# moire_v1_2_rt.net
KiCad netlist of a schematic drawn in EAGLE
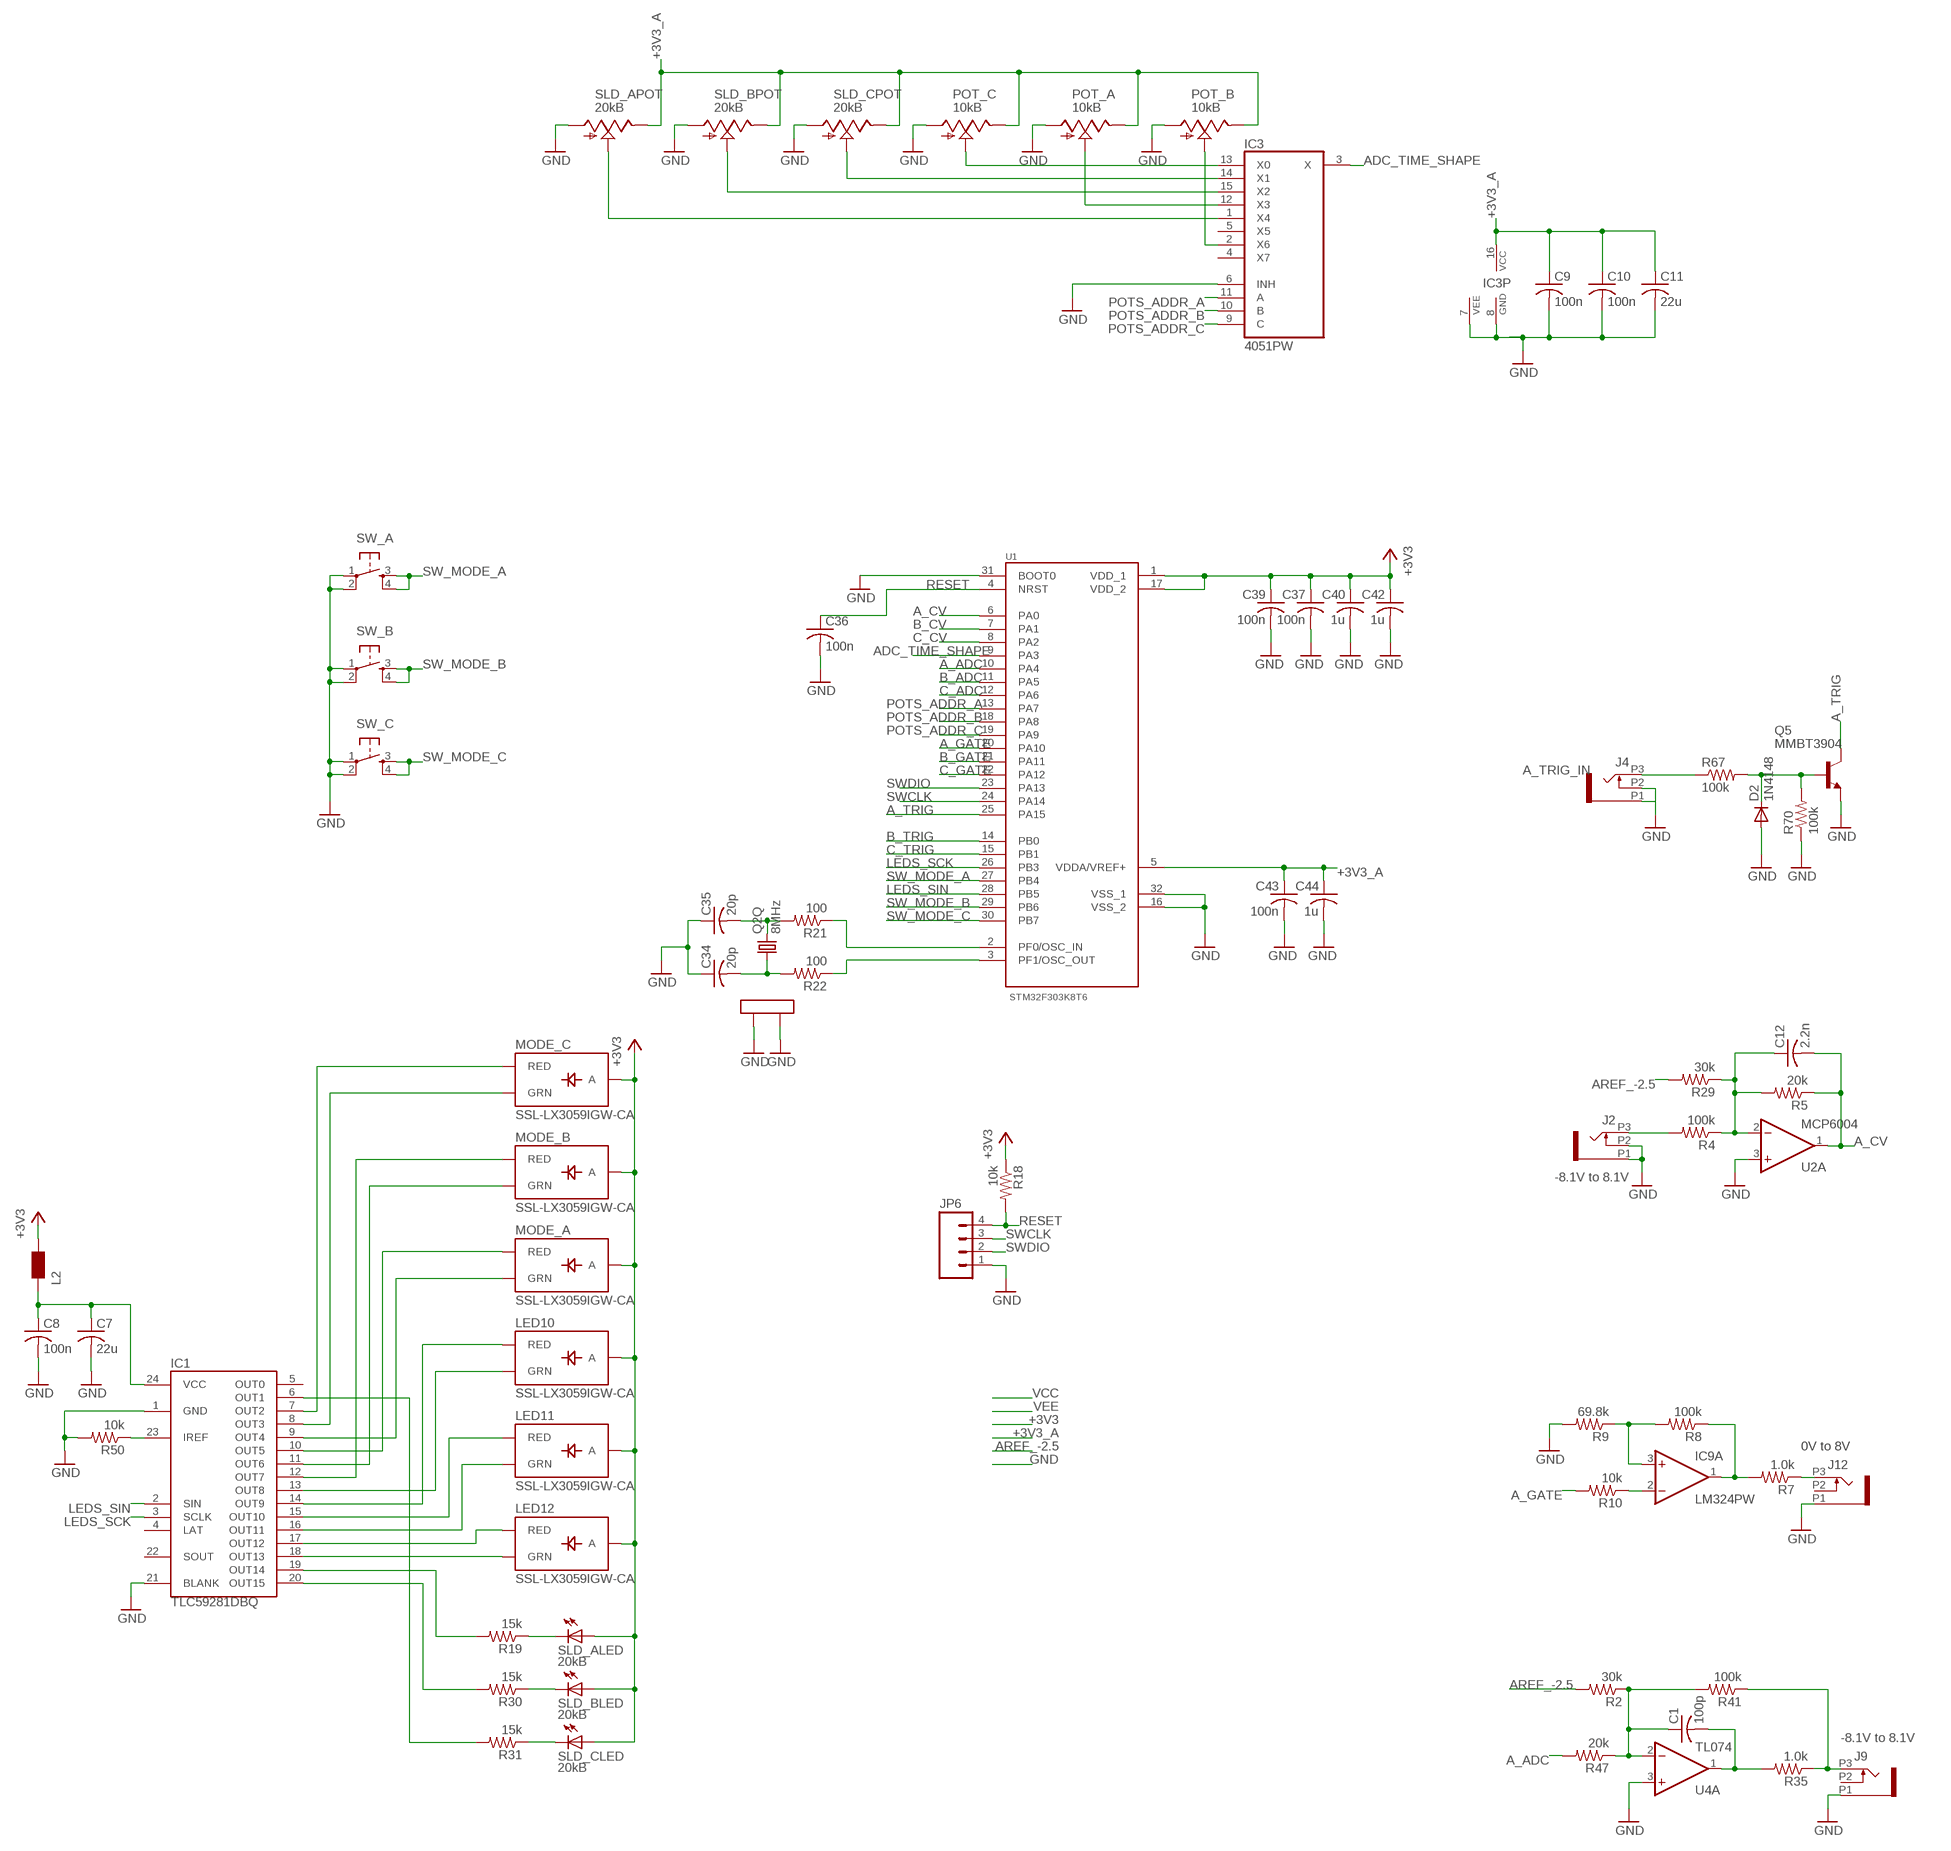
[diagram p0: schematic, sheet 1, part 1 of 2]
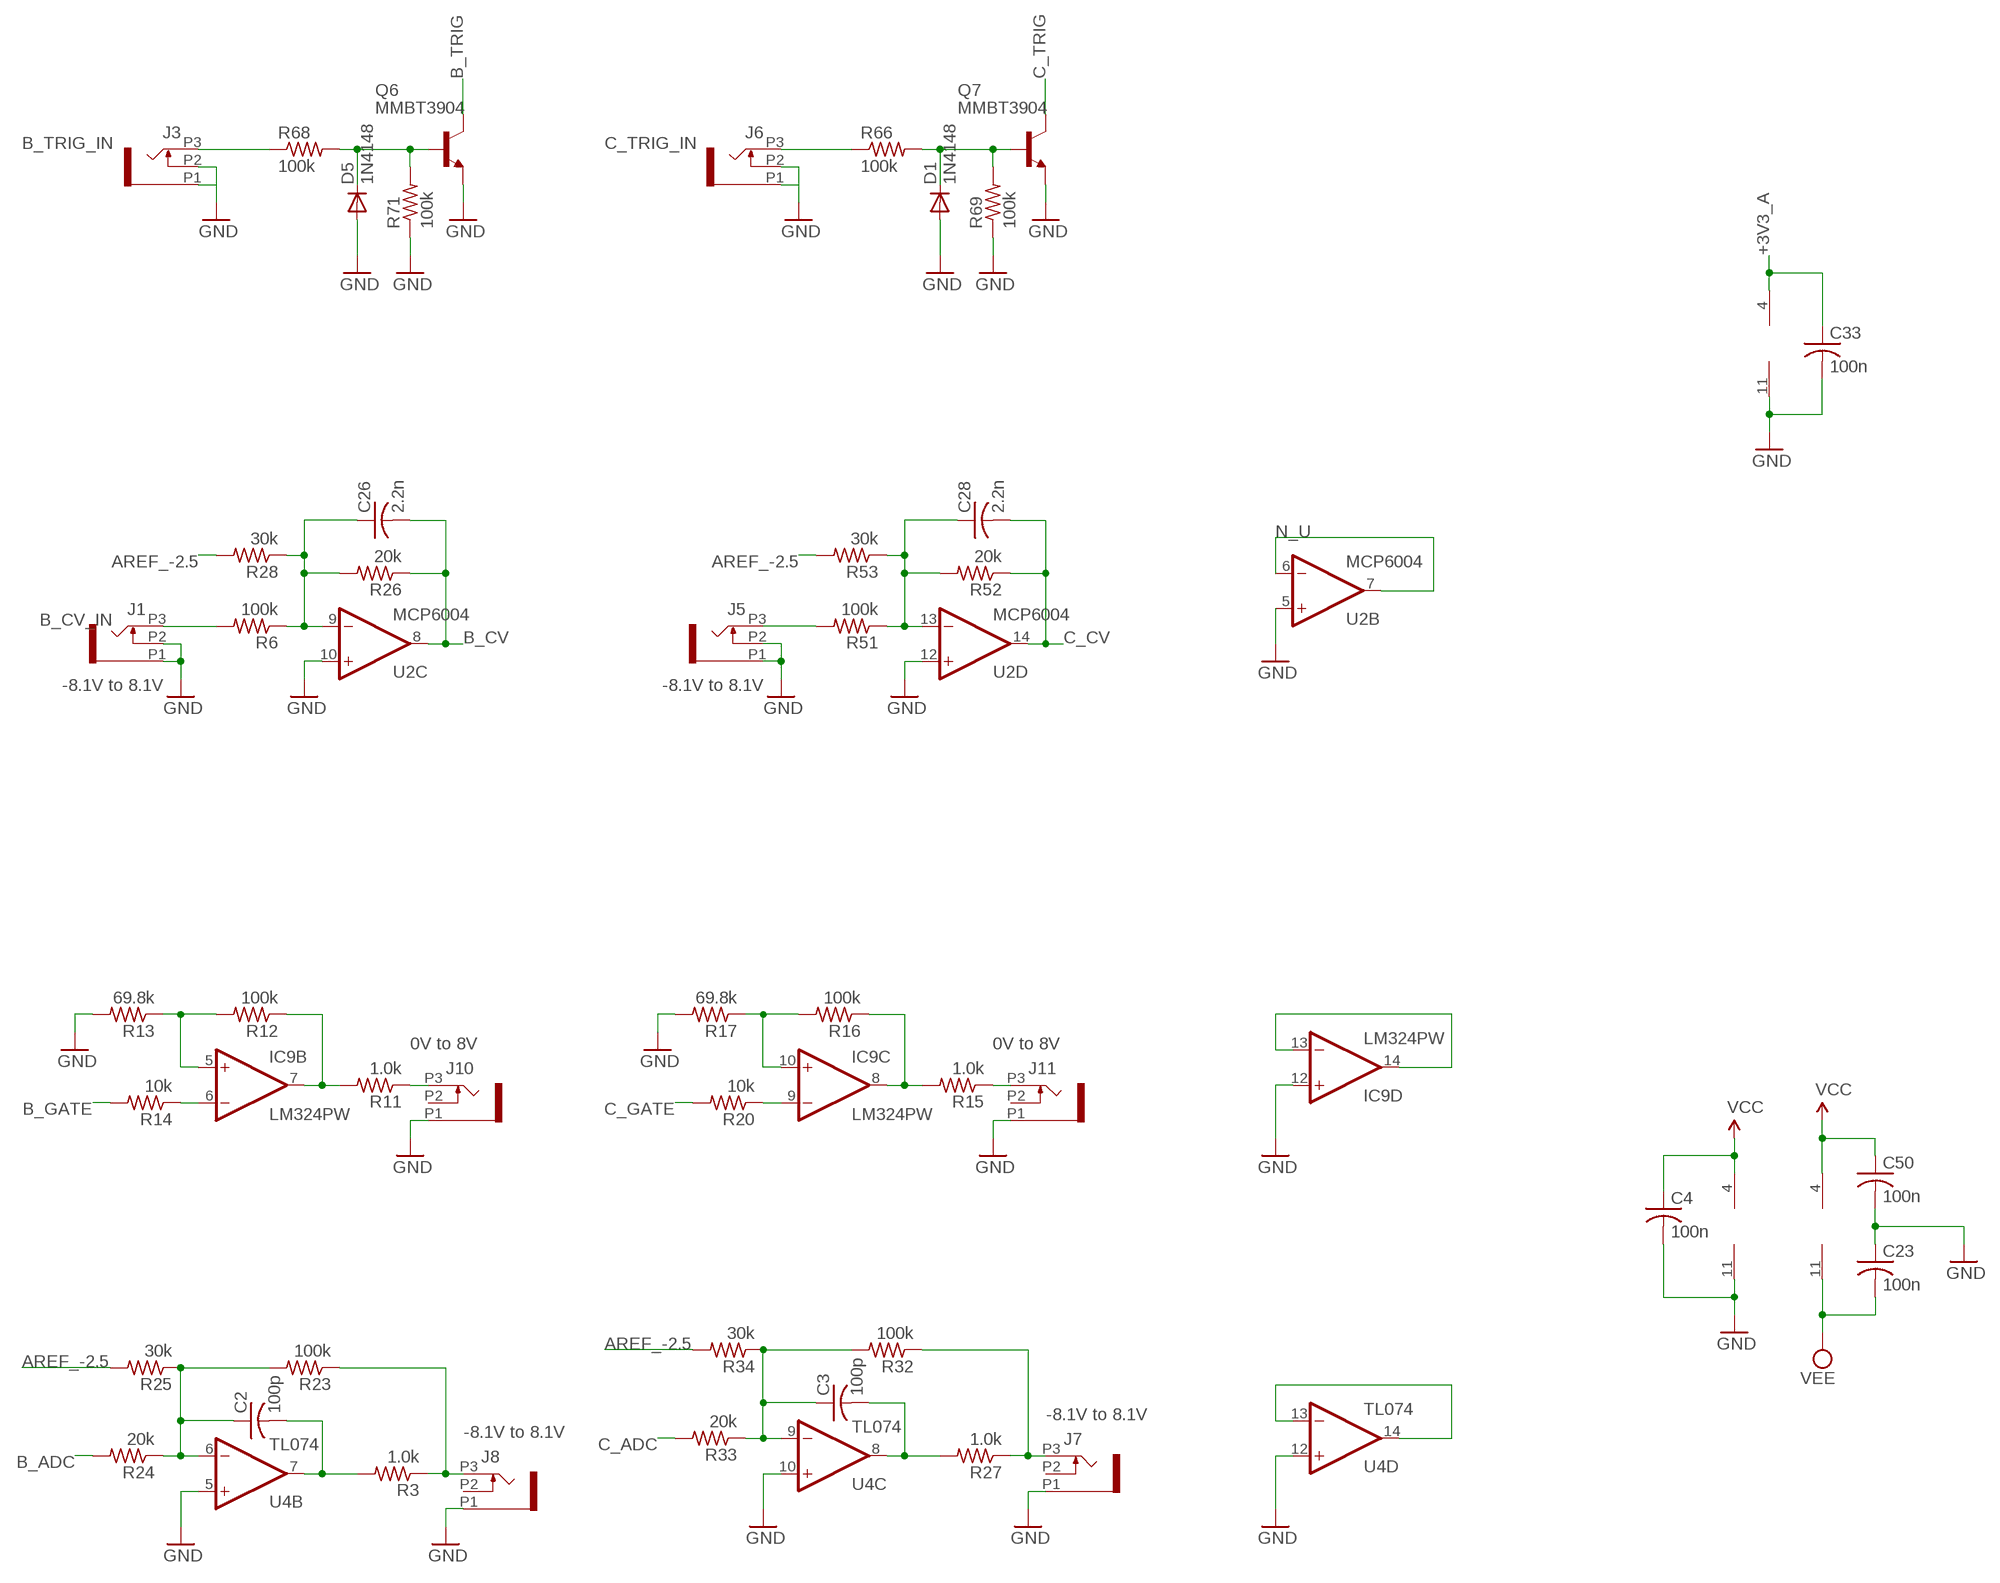
[diagram p1: schematic, sheet 1, part 2 of 2]
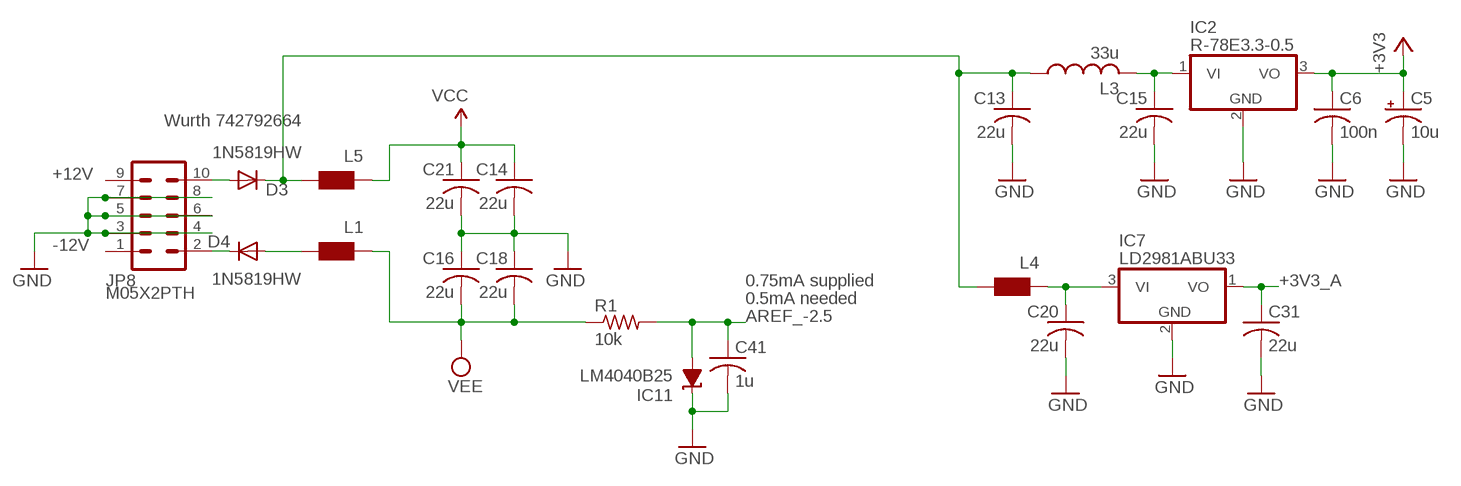
[diagram p2: schematic, sheet 2]

(export (version "E")
  (design (tool "Eeschema 10.0.6"))
  (components
    (comp (ref "C1")
      (value "100p")
      (footprint "eagle-import:C0603")
      (libsource (lib "eagle-import") (part "C-USC0603"))
    )
    (comp (ref "C2")
      (value "100p")
      (footprint "eagle-import:C0603")
      (libsource (lib "eagle-import") (part "C-USC0603"))
    )
    (comp (ref "C3")
      (value "100p")
      (footprint "eagle-import:C0603")
      (libsource (lib "eagle-import") (part "C-USC0603"))
    )
    (comp (ref "C4")
      (value "100n")
      (footprint "eagle-import:C0603")
      (libsource (lib "eagle-import") (part "C-USC0603"))
    )
    (comp (ref "C7")
      (value "22u")
      (footprint "eagle-import:C1206")
      (libsource (lib "eagle-import") (part "C-USC1206"))
    )
    (comp (ref "C8")
      (value "100n")
      (footprint "eagle-import:C0603")
      (libsource (lib "eagle-import") (part "C-USC0603"))
    )
    (comp (ref "C9")
      (value "100n")
      (footprint "eagle-import:C0603")
      (libsource (lib "eagle-import") (part "C-USC0603"))
    )
    (comp (ref "C10")
      (value "100n")
      (footprint "eagle-import:C0603")
      (libsource (lib "eagle-import") (part "C-USC0603"))
    )
    (comp (ref "C11")
      (value "22u")
      (footprint "eagle-import:C1206")
      (libsource (lib "eagle-import") (part "C-USC1206"))
    )
    (comp (ref "C12")
      (value "2.2n")
      (footprint "eagle-import:C0603")
      (libsource (lib "eagle-import") (part "C-USC0603"))
    )
    (comp (ref "C23")
      (value "100n")
      (footprint "eagle-import:C0603")
      (libsource (lib "eagle-import") (part "C-USC0603"))
    )
    (comp (ref "C26")
      (value "2.2n")
      (footprint "eagle-import:C0603")
      (libsource (lib "eagle-import") (part "C-USC0603"))
    )
    (comp (ref "C28")
      (value "2.2n")
      (footprint "eagle-import:C0603")
      (libsource (lib "eagle-import") (part "C-USC0603"))
    )
    (comp (ref "C33")
      (value "100n")
      (footprint "eagle-import:C0603")
      (libsource (lib "eagle-import") (part "C-USC0603"))
    )
    (comp (ref "C34")
      (value "20p")
      (footprint "eagle-import:C0603")
      (libsource (lib "eagle-import") (part "C-USC0603"))
    )
    (comp (ref "C35")
      (value "20p")
      (footprint "eagle-import:C0603")
      (libsource (lib "eagle-import") (part "C-USC0603"))
    )
    (comp (ref "C36")
      (value "100n")
      (footprint "eagle-import:C0603")
      (libsource (lib "eagle-import") (part "C-USC0603"))
    )
    (comp (ref "C37")
      (value "100n")
      (footprint "eagle-import:C0603")
      (libsource (lib "eagle-import") (part "C-USC0603"))
    )
    (comp (ref "C39")
      (value "100n")
      (footprint "eagle-import:C0603")
      (libsource (lib "eagle-import") (part "C-USC0603"))
    )
    (comp (ref "C40")
      (value "1u")
      (footprint "eagle-import:C0603")
      (libsource (lib "eagle-import") (part "C-USC0603"))
    )
    (comp (ref "C42")
      (value "1u")
      (footprint "eagle-import:C0603")
      (libsource (lib "eagle-import") (part "C-USC0603"))
    )
    (comp (ref "C43")
      (value "100n")
      (footprint "eagle-import:C0603")
      (libsource (lib "eagle-import") (part "C-USC0603"))
    )
    (comp (ref "C44")
      (value "1u")
      (footprint "eagle-import:C0603")
      (libsource (lib "eagle-import") (part "C-USC0603"))
    )
    (comp (ref "C50")
      (value "100n")
      (footprint "eagle-import:C0603")
      (libsource (lib "eagle-import") (part "C-USC0603"))
    )
    (comp (ref "D1")
      (value "1N4148")
      (footprint "eagle-import:SOD523")
      (libsource (lib "eagle-import") (part "DIODE-SOD523"))
    )
    (comp (ref "D2")
      (value "1N4148")
      (footprint "eagle-import:SOD523")
      (libsource (lib "eagle-import") (part "DIODE-SOD523"))
    )
    (comp (ref "D5")
      (value "1N4148")
      (footprint "eagle-import:SOD523")
      (libsource (lib "eagle-import") (part "DIODE-SOD523"))
    )
    (comp (ref "IC1")
      (value "TLC59281DBQ")
      (footprint "eagle-import:TSSOP24_0635")
      (libsource (lib "eagle-import") (part "TLC59281DBQ"))
    )
    (comp (ref "IC3")
      (value "4051PW")
      (footprint "eagle-import:TSSOP16_065")
      (libsource (lib "eagle-import") (part "4051PW"))
    )
    (comp (ref "IC9")
      (value "LM324PW")
      (footprint "eagle-import:TSSOP14_065")
      (libsource (lib "eagle-import") (part "TL074PW"))
    )
    (comp (ref "J1")
      (value "PJ301_THONKICONN6")
      (footprint "eagle-import:WQP_PJ_301M6")
      (libsource (lib "eagle-import") (part "PJ301_THONKICONN6"))
    )
    (comp (ref "J2")
      (value "PJ301_THONKICONN6")
      (footprint "eagle-import:WQP_PJ_301M6")
      (libsource (lib "eagle-import") (part "PJ301_THONKICONN6"))
    )
    (comp (ref "J3")
      (value "PJ301_THONKICONN6")
      (footprint "eagle-import:WQP_PJ_301M6")
      (libsource (lib "eagle-import") (part "PJ301_THONKICONN6"))
    )
    (comp (ref "J4")
      (value "PJ301_THONKICONN6")
      (footprint "eagle-import:WQP_PJ_301M6")
      (libsource (lib "eagle-import") (part "PJ301_THONKICONN6"))
    )
    (comp (ref "J5")
      (value "PJ301_THONKICONN6")
      (footprint "eagle-import:WQP_PJ_301M6")
      (libsource (lib "eagle-import") (part "PJ301_THONKICONN6"))
    )
    (comp (ref "J6")
      (value "PJ301_THONKICONN6")
      (footprint "eagle-import:WQP_PJ_301M6")
      (libsource (lib "eagle-import") (part "PJ301_THONKICONN6"))
    )
    (comp (ref "J7")
      (value "PJ301_THONKICONN6")
      (footprint "eagle-import:WQP_PJ_301M6")
      (libsource (lib "eagle-import") (part "PJ301_THONKICONN6"))
    )
    (comp (ref "J8")
      (value "PJ301_THONKICONN6")
      (footprint "eagle-import:WQP_PJ_301M6")
      (libsource (lib "eagle-import") (part "PJ301_THONKICONN6"))
    )
    (comp (ref "J9")
      (value "PJ301_THONKICONN6")
      (footprint "eagle-import:WQP_PJ_301M6")
      (libsource (lib "eagle-import") (part "PJ301_THONKICONN6"))
    )
    (comp (ref "J10")
      (value "PJ301_THONKICONN6")
      (footprint "eagle-import:WQP_PJ_301M6")
      (libsource (lib "eagle-import") (part "PJ301_THONKICONN6"))
    )
    (comp (ref "J11")
      (value "PJ301_THONKICONN6")
      (footprint "eagle-import:WQP_PJ_301M6")
      (libsource (lib "eagle-import") (part "PJ301_THONKICONN6"))
    )
    (comp (ref "J12")
      (value "PJ301_THONKICONN6")
      (footprint "eagle-import:WQP_PJ_301M6")
      (libsource (lib "eagle-import") (part "PJ301_THONKICONN6"))
    )
    (comp (ref "JP6")
      (value "M04PTH")
      (footprint "eagle-import:1X04")
      (libsource (lib "eagle-import") (part "M04PTH"))
    )
    (comp (ref "L2")
      (value "WE-CBF_0603")
      (footprint "eagle-import:0603")
      (libsource (lib "eagle-import") (part "WE-CBF_0603"))
    )
    (comp (ref "LED10")
      (value "SSL-LX3059IGW-CA")
      (footprint "eagle-import:LED-BICOLOR-THROUGHHOLE-LUMEX")
      (libsource (lib "eagle-import") (part "LED-BICOLOR-THROUGHHOLE-CA"))
    )
    (comp (ref "LED11")
      (value "SSL-LX3059IGW-CA")
      (footprint "eagle-import:LED-BICOLOR-THROUGHHOLE-LUMEX")
      (libsource (lib "eagle-import") (part "LED-BICOLOR-THROUGHHOLE-CA"))
    )
    (comp (ref "LED12")
      (value "SSL-LX3059IGW-CA")
      (footprint "eagle-import:LED-BICOLOR-THROUGHHOLE-LUMEX")
      (libsource (lib "eagle-import") (part "LED-BICOLOR-THROUGHHOLE-CA"))
    )
    (comp (ref "MODE_A")
      (value "SSL-LX3059IGW-CA")
      (footprint "eagle-import:LED-BICOLOR-THROUGHHOLE-LUMEX")
      (libsource (lib "eagle-import") (part "LED-BICOLOR-THROUGHHOLE-CA"))
    )
    (comp (ref "MODE_B")
      (value "SSL-LX3059IGW-CA")
      (footprint "eagle-import:LED-BICOLOR-THROUGHHOLE-LUMEX")
      (libsource (lib "eagle-import") (part "LED-BICOLOR-THROUGHHOLE-CA"))
    )
    (comp (ref "MODE_C")
      (value "SSL-LX3059IGW-CA")
      (footprint "eagle-import:LED-BICOLOR-THROUGHHOLE-LUMEX")
      (libsource (lib "eagle-import") (part "LED-BICOLOR-THROUGHHOLE-CA"))
    )
    (comp (ref "POT_A")
      (value "10kB")
      (footprint "eagle-import:ALPS_POT_VERTICAL")
      (libsource (lib "eagle-import") (part "POT_USVERTICAL"))
    )
    (comp (ref "POT_B")
      (value "10kB")
      (footprint "eagle-import:ALPS_POT_VERTICAL")
      (libsource (lib "eagle-import") (part "POT_USVERTICAL"))
    )
    (comp (ref "POT_C")
      (value "10kB")
      (footprint "eagle-import:ALPS_POT_VERTICAL")
      (libsource (lib "eagle-import") (part "POT_USVERTICAL"))
    )
    (comp (ref "Q2")
      (value "8MHz")
      (footprint "eagle-import:CTS406")
      (libsource (lib "eagle-import") (part "CRYSTAL"))
    )
    (comp (ref "Q5")
      (value "MMBT3904")
      (footprint "eagle-import:SOT23-BEC")
      (libsource (lib "eagle-import") (part "-NPN-SOT23-BECMMBT3904LT1"))
    )
    (comp (ref "Q6")
      (value "MMBT3904")
      (footprint "eagle-import:SOT23-BEC")
      (libsource (lib "eagle-import") (part "-NPN-SOT23-BECMMBT3904LT1"))
    )
    (comp (ref "Q7")
      (value "MMBT3904")
      (footprint "eagle-import:SOT23-BEC")
      (libsource (lib "eagle-import") (part "-NPN-SOT23-BECMMBT3904LT1"))
    )
    (comp (ref "R2")
      (value "30k")
      (footprint "eagle-import:R0603")
      (libsource (lib "eagle-import") (part "R-US_R0603"))
    )
    (comp (ref "R3")
      (value "1.0k")
      (footprint "eagle-import:R0603")
      (libsource (lib "eagle-import") (part "R-US_R0603"))
    )
    (comp (ref "R4")
      (value "100k")
      (footprint "eagle-import:R0603")
      (libsource (lib "eagle-import") (part "R-US_R0603"))
    )
    (comp (ref "R5")
      (value "20k")
      (footprint "eagle-import:R0603")
      (libsource (lib "eagle-import") (part "R-US_R0603"))
    )
    (comp (ref "R6")
      (value "100k")
      (footprint "eagle-import:R0603")
      (libsource (lib "eagle-import") (part "R-US_R0603"))
    )
    (comp (ref "R7")
      (value "1.0k")
      (footprint "eagle-import:R0603")
      (libsource (lib "eagle-import") (part "R-US_R0603"))
    )
    (comp (ref "R8")
      (value "100k")
      (footprint "eagle-import:R0603")
      (libsource (lib "eagle-import") (part "R-US_R0603"))
    )
    (comp (ref "R9")
      (value "69.8k")
      (footprint "eagle-import:R0603")
      (libsource (lib "eagle-import") (part "R-US_R0603"))
    )
    (comp (ref "R10")
      (value "10k")
      (footprint "eagle-import:R0603")
      (libsource (lib "eagle-import") (part "R-US_R0603"))
    )
    (comp (ref "R11")
      (value "1.0k")
      (footprint "eagle-import:R0603")
      (libsource (lib "eagle-import") (part "R-US_R0603"))
    )
    (comp (ref "R12")
      (value "100k")
      (footprint "eagle-import:R0603")
      (libsource (lib "eagle-import") (part "R-US_R0603"))
    )
    (comp (ref "R13")
      (value "69.8k")
      (footprint "eagle-import:R0603")
      (libsource (lib "eagle-import") (part "R-US_R0603"))
    )
    (comp (ref "R14")
      (value "10k")
      (footprint "eagle-import:R0603")
      (libsource (lib "eagle-import") (part "R-US_R0603"))
    )
    (comp (ref "R15")
      (value "1.0k")
      (footprint "eagle-import:R0603")
      (libsource (lib "eagle-import") (part "R-US_R0603"))
    )
    (comp (ref "R16")
      (value "100k")
      (footprint "eagle-import:R0603")
      (libsource (lib "eagle-import") (part "R-US_R0603"))
    )
    (comp (ref "R17")
      (value "69.8k")
      (footprint "eagle-import:R0603")
      (libsource (lib "eagle-import") (part "R-US_R0603"))
    )
    (comp (ref "R18")
      (value "10k")
      (footprint "eagle-import:R0603")
      (libsource (lib "eagle-import") (part "R-US_R0603"))
    )
    (comp (ref "R19")
      (value "15k")
      (footprint "eagle-import:R0603")
      (libsource (lib "eagle-import") (part "R-US_R0603"))
    )
    (comp (ref "R20")
      (value "10k")
      (footprint "eagle-import:R0603")
      (libsource (lib "eagle-import") (part "R-US_R0603"))
    )
    (comp (ref "R21")
      (value "100")
      (footprint "eagle-import:R0603")
      (libsource (lib "eagle-import") (part "R-US_R0603"))
    )
    (comp (ref "R22")
      (value "100")
      (footprint "eagle-import:R0603")
      (libsource (lib "eagle-import") (part "R-US_R0603"))
    )
    (comp (ref "R23")
      (value "100k")
      (footprint "eagle-import:R0603")
      (libsource (lib "eagle-import") (part "R-US_R0603"))
    )
    (comp (ref "R24")
      (value "20k")
      (footprint "eagle-import:R0603")
      (libsource (lib "eagle-import") (part "R-US_R0603"))
    )
    (comp (ref "R25")
      (value "30k")
      (footprint "eagle-import:R0603")
      (libsource (lib "eagle-import") (part "R-US_R0603"))
    )
    (comp (ref "R26")
      (value "20k")
      (footprint "eagle-import:R0603")
      (libsource (lib "eagle-import") (part "R-US_R0603"))
    )
    (comp (ref "R27")
      (value "1.0k")
      (footprint "eagle-import:R0603")
      (libsource (lib "eagle-import") (part "R-US_R0603"))
    )
    (comp (ref "R28")
      (value "30k")
      (footprint "eagle-import:R0603")
      (libsource (lib "eagle-import") (part "R-US_R0603"))
    )
    (comp (ref "R29")
      (value "30k")
      (footprint "eagle-import:R0603")
      (libsource (lib "eagle-import") (part "R-US_R0603"))
    )
    (comp (ref "R30")
      (value "15k")
      (footprint "eagle-import:R0603")
      (libsource (lib "eagle-import") (part "R-US_R0603"))
    )
    (comp (ref "R31")
      (value "15k")
      (footprint "eagle-import:R0603")
      (libsource (lib "eagle-import") (part "R-US_R0603"))
    )
    (comp (ref "R32")
      (value "100k")
      (footprint "eagle-import:R0603")
      (libsource (lib "eagle-import") (part "R-US_R0603"))
    )
    (comp (ref "R33")
      (value "20k")
      (footprint "eagle-import:R0603")
      (libsource (lib "eagle-import") (part "R-US_R0603"))
    )
    (comp (ref "R34")
      (value "30k")
      (footprint "eagle-import:R0603")
      (libsource (lib "eagle-import") (part "R-US_R0603"))
    )
    (comp (ref "R35")
      (value "1.0k")
      (footprint "eagle-import:R0603")
      (libsource (lib "eagle-import") (part "R-US_R0603"))
    )
    (comp (ref "R41")
      (value "100k")
      (footprint "eagle-import:R0603")
      (libsource (lib "eagle-import") (part "R-US_R0603"))
    )
    (comp (ref "R47")
      (value "20k")
      (footprint "eagle-import:R0603")
      (libsource (lib "eagle-import") (part "R-US_R0603"))
    )
    (comp (ref "R50")
      (value "10k")
      (footprint "eagle-import:R0603")
      (libsource (lib "eagle-import") (part "R-US_R0603"))
    )
    (comp (ref "R51")
      (value "100k")
      (footprint "eagle-import:R0603")
      (libsource (lib "eagle-import") (part "R-US_R0603"))
    )
    (comp (ref "R52")
      (value "20k")
      (footprint "eagle-import:R0603")
      (libsource (lib "eagle-import") (part "R-US_R0603"))
    )
    (comp (ref "R53")
      (value "30k")
      (footprint "eagle-import:R0603")
      (libsource (lib "eagle-import") (part "R-US_R0603"))
    )
    (comp (ref "R66")
      (value "100k")
      (footprint "eagle-import:R0603")
      (libsource (lib "eagle-import") (part "R-US_R0603"))
    )
    (comp (ref "R67")
      (value "100k")
      (footprint "eagle-import:R0603")
      (libsource (lib "eagle-import") (part "R-US_R0603"))
    )
    (comp (ref "R68")
      (value "100k")
      (footprint "eagle-import:R0603")
      (libsource (lib "eagle-import") (part "R-US_R0603"))
    )
    (comp (ref "R69")
      (value "100k")
      (footprint "eagle-import:R0603")
      (libsource (lib "eagle-import") (part "R-US_R0603"))
    )
    (comp (ref "R70")
      (value "100k")
      (footprint "eagle-import:R0603")
      (libsource (lib "eagle-import") (part "R-US_R0603"))
    )
    (comp (ref "R71")
      (value "100k")
      (footprint "eagle-import:R0603")
      (libsource (lib "eagle-import") (part "R-US_R0603"))
    )
    (comp (ref "SLD_A")
      (value "20kB")
      (footprint "eagle-import:BOURNS_SLIDER")
      (libsource (lib "eagle-import") (part "BOURNS_SLIDER"))
    )
    (comp (ref "SLD_B")
      (value "20kB")
      (footprint "eagle-import:BOURNS_SLIDER")
      (libsource (lib "eagle-import") (part "BOURNS_SLIDER"))
    )
    (comp (ref "SLD_C")
      (value "20kB")
      (footprint "eagle-import:BOURNS_SLIDER")
      (libsource (lib "eagle-import") (part "BOURNS_SLIDER"))
    )
    (comp (ref "SW_A")
      (value "TAC_SWITCHPTH")
      (footprint "eagle-import:TACTILE-PTH")
      (libsource (lib "eagle-import") (part "TAC_SWITCHPTH"))
    )
    (comp (ref "SW_B")
      (value "TAC_SWITCHPTH")
      (footprint "eagle-import:TACTILE-PTH")
      (libsource (lib "eagle-import") (part "TAC_SWITCHPTH"))
    )
    (comp (ref "SW_C")
      (value "TAC_SWITCHPTH")
      (footprint "eagle-import:TACTILE-PTH")
      (libsource (lib "eagle-import") (part "TAC_SWITCHPTH"))
    )
    (comp (ref "U1")
      (value "STM32F303K8T6")
      (footprint "eagle-import:QFP80P900X900X160-32N")
      (fields (field (name "MF") "STMicroelectronics"))
      (libsource (lib "eagle-import") (part "STM32F303K8T6"))
    )
    (comp (ref "U2")
      (value "MCP6004")
      (footprint "eagle-import:SO14")
      (libsource (lib "eagle-import") (part "MCP6004_SMD"))
    )
    (comp (ref "U4")
      (value "TL074")
      (footprint "eagle-import:SO14")
      (libsource (lib "eagle-import") (part "TL074_SMD"))
    )
    (comp (ref "C5")
      (value "10u")
      (footprint "eagle-import:PANASONIC_A")
      (libsource (lib "eagle-import") (part "CPOL-USA"))
    )
    (comp (ref "C6")
      (value "100n")
      (footprint "eagle-import:C0603")
      (libsource (lib "eagle-import") (part "C-USC0603"))
    )
    (comp (ref "C13")
      (value "22u")
      (footprint "eagle-import:C1206")
      (libsource (lib "eagle-import") (part "C-USC1206"))
    )
    (comp (ref "C14")
      (value "22u")
      (footprint "eagle-import:C1206")
      (libsource (lib "eagle-import") (part "C-USC1206"))
    )
    (comp (ref "C15")
      (value "22u")
      (footprint "eagle-import:C1206")
      (libsource (lib "eagle-import") (part "C-USC1206"))
    )
    (comp (ref "C16")
      (value "22u")
      (footprint "eagle-import:C1206")
      (libsource (lib "eagle-import") (part "C-USC1206"))
    )
    (comp (ref "C18")
      (value "22u")
      (footprint "eagle-import:C1206")
      (libsource (lib "eagle-import") (part "C-USC1206"))
    )
    (comp (ref "C20")
      (value "22u")
      (footprint "eagle-import:C1206")
      (libsource (lib "eagle-import") (part "C-USC1206"))
    )
    (comp (ref "C21")
      (value "22u")
      (footprint "eagle-import:C1206")
      (libsource (lib "eagle-import") (part "C-USC1206"))
    )
    (comp (ref "C31")
      (value "22u")
      (footprint "eagle-import:C1206")
      (libsource (lib "eagle-import") (part "C-USC1206"))
    )
    (comp (ref "C41")
      (value "1u")
      (footprint "eagle-import:C0603")
      (libsource (lib "eagle-import") (part "C-USC0603"))
    )
    (comp (ref "D3")
      (value "1N5819HW")
      (footprint "eagle-import:SOD123")
      (libsource (lib "eagle-import") (part "DIODE-SOD123"))
    )
    (comp (ref "D4")
      (value "1N5819HW")
      (footprint "eagle-import:SOD123")
      (libsource (lib "eagle-import") (part "DIODE-SOD123"))
    )
    (comp (ref "IC2")
      (value "R-78E3.3-0.5")
      (footprint "eagle-import:WE78")
      (libsource (lib "eagle-import") (part "WE173950378"))
    )
    (comp (ref "IC7")
      (value "LD2981ABU33")
      (footprint "eagle-import:SOT89")
      (libsource (lib "eagle-import") (part "LD2981ABU"))
    )
    (comp (ref "IC11")
      (value "LM4040B25")
      (footprint "eagle-import:DBZ_R-PDSO-G3")
      (libsource (lib "eagle-import") (part "LM4041DBZB12"))
    )
    (comp (ref "JP8")
      (value "M05X2PTH")
      (footprint "eagle-import:2X5-PTH")
      (libsource (lib "eagle-import") (part "M05X2PTH"))
    )
    (comp (ref "L1")
      (value "WE-CBF_0603")
      (footprint "eagle-import:0603")
      (libsource (lib "eagle-import") (part "WE-CBF_0603"))
    )
    (comp (ref "L3")
      (value "33u")
      (footprint "eagle-import:L2012C")
      (libsource (lib "eagle-import") (part "L-USL2012C"))
    )
    (comp (ref "L4")
      (value "WE-CBF_0603")
      (footprint "eagle-import:0603")
      (libsource (lib "eagle-import") (part "WE-CBF_0603"))
    )
    (comp (ref "L5")
      (value "WE-CBF_0603")
      (footprint "eagle-import:0603")
      (libsource (lib "eagle-import") (part "WE-CBF_0603"))
    )
    (comp (ref "R1")
      (value "10k")
      (footprint "eagle-import:R0603")
      (libsource (lib "eagle-import") (part "R-US_R0603"))
    )
  )
  (nets
    (net (code "1") (name "+3V3") (class "Default")
      (node (ref "C37") (pin "1") (pinfunction "1_1") (pintype "passive"))
      (node (ref "C39") (pin "1") (pinfunction "1_1") (pintype "passive"))
      (node (ref "C40") (pin "1") (pinfunction "1_1") (pintype "passive"))
      (node (ref "C42") (pin "1") (pinfunction "1_1") (pintype "passive"))
      (node (ref "C5") (pin "+") (pinfunction "+_+") (pintype "passive"))
      (node (ref "C6") (pin "1") (pinfunction "1_1") (pintype "passive"))
      (node (ref "IC2") (pin "3") (pinfunction "VO_3") (pintype "passive"))
      (node (ref "L2") (pin "2") (pinfunction "2_2") (pintype "passive"))
      (node (ref "LED10") (pin "A") (pinfunction "A_A") (pintype "bidirectional"))
      (node (ref "LED11") (pin "A") (pinfunction "A_A") (pintype "bidirectional"))
      (node (ref "LED12") (pin "A") (pinfunction "A_A") (pintype "bidirectional"))
      (node (ref "MODE_A") (pin "A") (pinfunction "A_A") (pintype "bidirectional"))
      (node (ref "MODE_B") (pin "A") (pinfunction "A_A") (pintype "bidirectional"))
      (node (ref "MODE_C") (pin "A") (pinfunction "A_A") (pintype "bidirectional"))
      (node (ref "R18") (pin "1") (pinfunction "1_1") (pintype "passive"))
      (node (ref "SLD_A") (pin "B") (pinfunction "A_B") (pintype "passive"))
      (node (ref "SLD_B") (pin "B") (pinfunction "A_B") (pintype "passive"))
      (node (ref "SLD_C") (pin "B") (pinfunction "A_B") (pintype "passive"))
      (node (ref "U1") (pin "1") (pinfunction "VDD_1_1") (pintype "power_in"))
      (node (ref "U1") (pin "17") (pinfunction "VDD_2_17") (pintype "power_in"))
    )
    (net (code "2") (name "+3V3_A") (class "Default")
      (node (ref "C10") (pin "1") (pinfunction "1_1") (pintype "passive"))
      (node (ref "C11") (pin "1") (pinfunction "1_1") (pintype "passive"))
      (node (ref "C31") (pin "1") (pinfunction "1_1") (pintype "passive"))
      (node (ref "C33") (pin "1") (pinfunction "1_1") (pintype "passive"))
      (node (ref "C43") (pin "1") (pinfunction "1_1") (pintype "passive"))
      (node (ref "C44") (pin "1") (pinfunction "1_1") (pintype "passive"))
      (node (ref "C9") (pin "1") (pinfunction "1_1") (pintype "passive"))
      (node (ref "IC3") (pin "16") (pinfunction "VCC_16") (pintype "power_in"))
      (node (ref "IC7") (pin "1") (pinfunction "VO_1") (pintype "passive"))
      (node (ref "POT_A") (pin "P$1") (pinfunction "E_P$1") (pintype "passive"))
      (node (ref "POT_B") (pin "P$1") (pinfunction "E_P$1") (pintype "passive"))
      (node (ref "POT_C") (pin "P$1") (pinfunction "E_P$1") (pintype "passive"))
      (node (ref "SLD_A") (pin "3") (pinfunction "E_3") (pintype "passive"))
      (node (ref "SLD_B") (pin "3") (pinfunction "E_3") (pintype "passive"))
      (node (ref "SLD_C") (pin "3") (pinfunction "E_3") (pintype "passive"))
      (node (ref "U1") (pin "5") (pinfunction "VDDA/VREF+_5") (pintype "power_in"))
      (node (ref "U2") (pin "4") (pinfunction "V+_4") (pintype "power_in"))
    )
    (net (code "3") (name "+12V") (class "Default")
      (node (ref "D3") (pin "A") (pinfunction "A_A") (pintype "passive"))
      (node (ref "JP8") (pin "10") (pinfunction "10_10") (pintype "passive"))
      (node (ref "JP8") (pin "9") (pinfunction "9_9") (pintype "passive"))
    )
    (net (code "4") (name "-12V") (class "Default")
      (node (ref "D4") (pin "C") (pinfunction "C_C") (pintype "passive"))
      (node (ref "JP8") (pin "1") (pinfunction "1_1") (pintype "passive"))
      (node (ref "JP8") (pin "2") (pinfunction "2_2") (pintype "passive"))
    )
    (net (code "5") (name "ADC_TIME_SHAPE") (class "Default")
      (node (ref "IC3") (pin "3") (pinfunction "X_3") (pintype "bidirectional"))
      (node (ref "U1") (pin "9") (pinfunction "PA3_9") (pintype "bidirectional"))
    )
    (net (code "6") (name "AREF_-2.5") (class "Default")
      (node (ref "C41") (pin "1") (pinfunction "1_1") (pintype "passive"))
      (node (ref "IC11") (pin "2") (pinfunction "A_2") (pintype "passive"))
      (node (ref "R1") (pin "2") (pinfunction "2_2") (pintype "passive"))
      (node (ref "R2") (pin "2") (pinfunction "2_2") (pintype "passive"))
      (node (ref "R25") (pin "2") (pinfunction "2_2") (pintype "passive"))
      (node (ref "R28") (pin "2") (pinfunction "2_2") (pintype "passive"))
      (node (ref "R29") (pin "2") (pinfunction "2_2") (pintype "passive"))
      (node (ref "R34") (pin "2") (pinfunction "2_2") (pintype "passive"))
      (node (ref "R53") (pin "2") (pinfunction "2_2") (pintype "passive"))
    )
    (net (code "7") (name "A_ADC") (class "Default")
      (node (ref "R47") (pin "2") (pinfunction "2_2") (pintype "passive"))
      (node (ref "U1") (pin "10") (pinfunction "PA4_10") (pintype "bidirectional"))
    )
    (net (code "8") (name "A_CV") (class "Default")
      (node (ref "C12") (pin "2") (pinfunction "2_2") (pintype "passive"))
      (node (ref "R5") (pin "1") (pinfunction "1_1") (pintype "passive"))
      (node (ref "U1") (pin "6") (pinfunction "PA0_6") (pintype "bidirectional"))
      (node (ref "U2") (pin "1") (pinfunction "OUT_1") (pintype "output"))
    )
    (net (code "9") (name "A_GATE") (class "Default")
      (node (ref "R10") (pin "2") (pinfunction "2_2") (pintype "passive"))
      (node (ref "U1") (pin "20") (pinfunction "PA10_20") (pintype "bidirectional"))
    )
    (net (code "10") (name "A_TRIG") (class "Default")
      (node (ref "Q5") (pin "C") (pinfunction "C_C") (pintype "passive"))
      (node (ref "U1") (pin "25") (pinfunction "PA15_25") (pintype "bidirectional"))
    )
    (net (code "11") (name "A_TRIG_IN") (class "Default")
      (node (ref "J4") (pin "P3") (pinfunction "3_P3") (pintype "passive"))
      (node (ref "R67") (pin "1") (pinfunction "1_1") (pintype "passive"))
    )
    (net (code "12") (name "B_ADC") (class "Default")
      (node (ref "R24") (pin "2") (pinfunction "2_2") (pintype "passive"))
      (node (ref "U1") (pin "11") (pinfunction "PA5_11") (pintype "bidirectional"))
    )
    (net (code "13") (name "B_CV") (class "Default")
      (node (ref "C26") (pin "2") (pinfunction "2_2") (pintype "passive"))
      (node (ref "R26") (pin "1") (pinfunction "1_1") (pintype "passive"))
      (node (ref "U1") (pin "7") (pinfunction "PA1_7") (pintype "bidirectional"))
      (node (ref "U2") (pin "8") (pinfunction "OUT_8") (pintype "output"))
    )
    (net (code "14") (name "B_CV_IN") (class "Default")
      (node (ref "J1") (pin "P3") (pinfunction "3_P3") (pintype "passive"))
      (node (ref "R6") (pin "2") (pinfunction "2_2") (pintype "passive"))
    )
    (net (code "15") (name "B_GATE") (class "Default")
      (node (ref "R14") (pin "2") (pinfunction "2_2") (pintype "passive"))
      (node (ref "U1") (pin "21") (pinfunction "PA11_21") (pintype "bidirectional"))
    )
    (net (code "16") (name "B_TRIG") (class "Default")
      (node (ref "Q6") (pin "C") (pinfunction "C_C") (pintype "passive"))
      (node (ref "U1") (pin "14") (pinfunction "PB0_14") (pintype "bidirectional"))
    )
    (net (code "17") (name "B_TRIG_IN") (class "Default")
      (node (ref "J3") (pin "P3") (pinfunction "3_P3") (pintype "passive"))
      (node (ref "R68") (pin "1") (pinfunction "1_1") (pintype "passive"))
    )
    (net (code "18") (name "C_ADC") (class "Default")
      (node (ref "R33") (pin "2") (pinfunction "2_2") (pintype "passive"))
      (node (ref "U1") (pin "12") (pinfunction "PA6_12") (pintype "bidirectional"))
    )
    (net (code "19") (name "C_CV") (class "Default")
      (node (ref "C28") (pin "2") (pinfunction "2_2") (pintype "passive"))
      (node (ref "R52") (pin "1") (pinfunction "1_1") (pintype "passive"))
      (node (ref "U1") (pin "8") (pinfunction "PA2_8") (pintype "bidirectional"))
      (node (ref "U2") (pin "14") (pinfunction "OUT_14") (pintype "output"))
    )
    (net (code "20") (name "C_GATE") (class "Default")
      (node (ref "R20") (pin "2") (pinfunction "2_2") (pintype "passive"))
      (node (ref "U1") (pin "22") (pinfunction "PA12_22") (pintype "bidirectional"))
    )
    (net (code "21") (name "C_TRIG") (class "Default")
      (node (ref "Q7") (pin "C") (pinfunction "C_C") (pintype "passive"))
      (node (ref "U1") (pin "15") (pinfunction "PB1_15") (pintype "bidirectional"))
    )
    (net (code "22") (name "C_TRIG_IN") (class "Default")
      (node (ref "J6") (pin "P3") (pinfunction "3_P3") (pintype "passive"))
      (node (ref "R66") (pin "1") (pinfunction "1_1") (pintype "passive"))
    )
    (net (code "23") (name "GND") (class "Default")
      (node (ref "C10") (pin "2") (pinfunction "2_2") (pintype "passive"))
      (node (ref "C11") (pin "2") (pinfunction "2_2") (pintype "passive"))
      (node (ref "C13") (pin "2") (pinfunction "2_2") (pintype "passive"))
      (node (ref "C14") (pin "2") (pinfunction "2_2") (pintype "passive"))
      (node (ref "C15") (pin "2") (pinfunction "2_2") (pintype "passive"))
      (node (ref "C16") (pin "1") (pinfunction "1_1") (pintype "passive"))
      (node (ref "C18") (pin "1") (pinfunction "1_1") (pintype "passive"))
      (node (ref "C20") (pin "2") (pinfunction "2_2") (pintype "passive"))
      (node (ref "C21") (pin "2") (pinfunction "2_2") (pintype "passive"))
      (node (ref "C23") (pin "1") (pinfunction "1_1") (pintype "passive"))
      (node (ref "C31") (pin "2") (pinfunction "2_2") (pintype "passive"))
      (node (ref "C33") (pin "2") (pinfunction "2_2") (pintype "passive"))
      (node (ref "C34") (pin "1") (pinfunction "1_1") (pintype "passive"))
      (node (ref "C35") (pin "1") (pinfunction "1_1") (pintype "passive"))
      (node (ref "C36") (pin "2") (pinfunction "2_2") (pintype "passive"))
      (node (ref "C37") (pin "2") (pinfunction "2_2") (pintype "passive"))
      (node (ref "C39") (pin "2") (pinfunction "2_2") (pintype "passive"))
      (node (ref "C4") (pin "2") (pinfunction "2_2") (pintype "passive"))
      (node (ref "C40") (pin "2") (pinfunction "2_2") (pintype "passive"))
      (node (ref "C41") (pin "2") (pinfunction "2_2") (pintype "passive"))
      (node (ref "C42") (pin "2") (pinfunction "2_2") (pintype "passive"))
      (node (ref "C43") (pin "2") (pinfunction "2_2") (pintype "passive"))
      (node (ref "C44") (pin "2") (pinfunction "2_2") (pintype "passive"))
      (node (ref "C5") (pin "-") (pinfunction "-_-") (pintype "passive"))
      (node (ref "C50") (pin "2") (pinfunction "2_2") (pintype "passive"))
      (node (ref "C6") (pin "2") (pinfunction "2_2") (pintype "passive"))
      (node (ref "C7") (pin "2") (pinfunction "2_2") (pintype "passive"))
      (node (ref "C8") (pin "2") (pinfunction "2_2") (pintype "passive"))
      (node (ref "C9") (pin "2") (pinfunction "2_2") (pintype "passive"))
      (node (ref "D1") (pin "A") (pinfunction "A_A") (pintype "passive"))
      (node (ref "D2") (pin "A") (pinfunction "A_A") (pintype "passive"))
      (node (ref "D5") (pin "A") (pinfunction "A_A") (pintype "passive"))
      (node (ref "IC1") (pin "1") (pinfunction "GND_1") (pintype "bidirectional"))
      (node (ref "IC1") (pin "21") (pinfunction "BLANK_21") (pintype "bidirectional"))
      (node (ref "IC11") (pin "1") (pinfunction "C_1") (pintype "passive"))
      (node (ref "IC2") (pin "2") (pinfunction "GND_2") (pintype "passive"))
      (node (ref "IC3") (pin "6") (pinfunction "INH_6") (pintype "input"))
      (node (ref "IC3") (pin "7") (pinfunction "VEE_7") (pintype "power_in"))
      (node (ref "IC3") (pin "8") (pinfunction "GND_8") (pintype "power_in"))
      (node (ref "IC7") (pin "2") (pinfunction "GND_2") (pintype "passive"))
      (node (ref "IC9") (pin "11") (pinfunction "V-_11") (pintype "power_in"))
      (node (ref "IC9") (pin "12") (pinfunction "+IN_12") (pintype "input"))
      (node (ref "J1") (pin "P1") (pinfunction "1_P1") (pintype "passive"))
      (node (ref "J1") (pin "P2") (pinfunction "2_P2") (pintype "passive"))
      (node (ref "J10") (pin "P1") (pinfunction "1_P1") (pintype "passive"))
      (node (ref "J11") (pin "P1") (pinfunction "1_P1") (pintype "passive"))
      (node (ref "J12") (pin "P1") (pinfunction "1_P1") (pintype "passive"))
      (node (ref "J2") (pin "P1") (pinfunction "1_P1") (pintype "passive"))
      (node (ref "J2") (pin "P2") (pinfunction "2_P2") (pintype "passive"))
      (node (ref "J3") (pin "P1") (pinfunction "1_P1") (pintype "passive"))
      (node (ref "J3") (pin "P2") (pinfunction "2_P2") (pintype "passive"))
      (node (ref "J4") (pin "P1") (pinfunction "1_P1") (pintype "passive"))
      (node (ref "J4") (pin "P2") (pinfunction "2_P2") (pintype "passive"))
      (node (ref "J5") (pin "P1") (pinfunction "1_P1") (pintype "passive"))
      (node (ref "J5") (pin "P2") (pinfunction "2_P2") (pintype "passive"))
      (node (ref "J6") (pin "P1") (pinfunction "1_P1") (pintype "passive"))
      (node (ref "J6") (pin "P2") (pinfunction "2_P2") (pintype "passive"))
      (node (ref "J7") (pin "P1") (pinfunction "1_P1") (pintype "passive"))
      (node (ref "J8") (pin "P1") (pinfunction "1_P1") (pintype "passive"))
      (node (ref "J9") (pin "P1") (pinfunction "1_P1") (pintype "passive"))
      (node (ref "JP6") (pin "1") (pinfunction "1_1") (pintype "passive"))
      (node (ref "JP8") (pin "3") (pinfunction "3_3") (pintype "passive"))
      (node (ref "JP8") (pin "4") (pinfunction "4_4") (pintype "passive"))
      (node (ref "JP8") (pin "5") (pinfunction "5_5") (pintype "passive"))
      (node (ref "JP8") (pin "6") (pinfunction "6_6") (pintype "passive"))
      (node (ref "JP8") (pin "7") (pinfunction "7_7") (pintype "passive"))
      (node (ref "JP8") (pin "8") (pinfunction "8_8") (pintype "passive"))
      (node (ref "POT_A") (pin "P$3") (pinfunction "A_P$3") (pintype "passive"))
      (node (ref "POT_B") (pin "P$3") (pinfunction "A_P$3") (pintype "passive"))
      (node (ref "POT_C") (pin "P$3") (pinfunction "A_P$3") (pintype "passive"))
      (node (ref "Q2") (pin "2") (pinfunction "LID1_2") (pintype "power_in"))
      (node (ref "Q2") (pin "4") (pinfunction "LID2_4") (pintype "power_in"))
      (node (ref "Q5") (pin "E") (pinfunction "E_E") (pintype "passive"))
      (node (ref "Q6") (pin "E") (pinfunction "E_E") (pintype "passive"))
      (node (ref "Q7") (pin "E") (pinfunction "E_E") (pintype "passive"))
      (node (ref "R13") (pin "2") (pinfunction "2_2") (pintype "passive"))
      (node (ref "R17") (pin "2") (pinfunction "2_2") (pintype "passive"))
      (node (ref "R50") (pin "2") (pinfunction "2_2") (pintype "passive"))
      (node (ref "R69") (pin "1") (pinfunction "1_1") (pintype "passive"))
      (node (ref "R70") (pin "1") (pinfunction "1_1") (pintype "passive"))
      (node (ref "R71") (pin "1") (pinfunction "1_1") (pintype "passive"))
      (node (ref "R9") (pin "2") (pinfunction "2_2") (pintype "passive"))
      (node (ref "SLD_A") (pin "1") (pinfunction "A_1") (pintype "passive"))
      (node (ref "SLD_B") (pin "1") (pinfunction "A_1") (pintype "passive"))
      (node (ref "SLD_C") (pin "1") (pinfunction "A_1") (pintype "passive"))
      (node (ref "SW_A") (pin "1") (pinfunction "1_1") (pintype "passive"))
      (node (ref "SW_A") (pin "2") (pinfunction "2_2") (pintype "passive"))
      (node (ref "SW_B") (pin "1") (pinfunction "1_1") (pintype "passive"))
      (node (ref "SW_B") (pin "2") (pinfunction "2_2") (pintype "passive"))
      (node (ref "SW_C") (pin "1") (pinfunction "1_1") (pintype "passive"))
      (node (ref "SW_C") (pin "2") (pinfunction "2_2") (pintype "passive"))
      (node (ref "U1") (pin "16") (pinfunction "VSS_2_16") (pintype "power_in"))
      (node (ref "U1") (pin "31") (pinfunction "BOOT0_31") (pintype "input"))
      (node (ref "U1") (pin "32") (pinfunction "VSS_1_32") (pintype "power_in"))
      (node (ref "U2") (pin "10") (pinfunction "+IN_10") (pintype "input"))
      (node (ref "U2") (pin "11") (pinfunction "V-_11") (pintype "power_in"))
      (node (ref "U2") (pin "12") (pinfunction "+IN_12") (pintype "input"))
      (node (ref "U2") (pin "3") (pinfunction "+IN_3") (pintype "input"))
      (node (ref "U2") (pin "5") (pinfunction "+IN_5") (pintype "input"))
      (node (ref "U4") (pin "10") (pinfunction "+IN_10") (pintype "input"))
      (node (ref "U4") (pin "12") (pinfunction "+IN_12") (pintype "input"))
      (node (ref "U4") (pin "3") (pinfunction "+IN_3") (pintype "input"))
      (node (ref "U4") (pin "5") (pinfunction "+IN_5") (pintype "input"))
    )
    (net (code "24") (name "LEDS_SCK") (class "Default")
      (node (ref "IC1") (pin "3") (pinfunction "SCLK_3") (pintype "bidirectional"))
      (node (ref "U1") (pin "26") (pinfunction "PB3_26") (pintype "bidirectional"))
    )
    (net (code "25") (name "LEDS_SIN") (class "Default")
      (node (ref "IC1") (pin "2") (pinfunction "SIN_2") (pintype "bidirectional"))
      (node (ref "U1") (pin "28") (pinfunction "PB5_28") (pintype "bidirectional"))
    )
    (net (code "26") (name "N_U") (class "Default")
      (node (ref "U2") (pin "6") (pinfunction "-IN_6") (pintype "input"))
      (node (ref "U2") (pin "7") (pinfunction "OUT_7") (pintype "output"))
    )
    (net (code "27") (name "Net-(C13-Pad1)") (class "Default")
      (node (ref "C13") (pin "1") (pinfunction "1_1") (pintype "passive"))
      (node (ref "D3") (pin "C") (pinfunction "C_C") (pintype "passive"))
      (node (ref "L3") (pin "1") (pinfunction "1_1") (pintype "passive"))
      (node (ref "L4") (pin "2") (pinfunction "2_2") (pintype "passive"))
      (node (ref "L5") (pin "2") (pinfunction "2_2") (pintype "passive"))
    )
    (net (code "28") (name "Net-(C34-Pad2)") (class "Default")
      (node (ref "C34") (pin "2") (pinfunction "2_2") (pintype "passive"))
      (node (ref "Q2") (pin "1") (pinfunction "1_1") (pintype "passive"))
      (node (ref "R22") (pin "2") (pinfunction "2_2") (pintype "passive"))
    )
    (net (code "29") (name "Net-(D1-PadC)") (class "Default")
      (node (ref "D1") (pin "C") (pinfunction "C_C") (pintype "passive"))
      (node (ref "Q7") (pin "B") (pinfunction "B_B") (pintype "passive"))
      (node (ref "R66") (pin "2") (pinfunction "2_2") (pintype "passive"))
      (node (ref "R69") (pin "2") (pinfunction "2_2") (pintype "passive"))
    )
    (net (code "30") (name "Net-(D2-PadC)") (class "Default")
      (node (ref "D2") (pin "C") (pinfunction "C_C") (pintype "passive"))
      (node (ref "Q5") (pin "B") (pinfunction "B_B") (pintype "passive"))
      (node (ref "R67") (pin "2") (pinfunction "2_2") (pintype "passive"))
      (node (ref "R70") (pin "2") (pinfunction "2_2") (pintype "passive"))
    )
    (net (code "31") (name "Net-(D4-PadA)") (class "Default")
      (node (ref "D4") (pin "A") (pinfunction "A_A") (pintype "passive"))
      (node (ref "L1") (pin "2") (pinfunction "2_2") (pintype "passive"))
    )
    (net (code "32") (name "Net-(D5-PadC)") (class "Default")
      (node (ref "D5") (pin "C") (pinfunction "C_C") (pintype "passive"))
      (node (ref "Q6") (pin "B") (pinfunction "B_B") (pintype "passive"))
      (node (ref "R68") (pin "2") (pinfunction "2_2") (pintype "passive"))
      (node (ref "R71") (pin "2") (pinfunction "2_2") (pintype "passive"))
    )
    (net (code "33") (name "Net-(IC1-IREF)") (class "Default")
      (node (ref "IC1") (pin "23") (pinfunction "IREF_23") (pintype "bidirectional"))
      (node (ref "R50") (pin "1") (pinfunction "1_1") (pintype "passive"))
    )
    (net (code "34") (name "Net-(IC1-OUT1)") (class "Default")
      (node (ref "IC1") (pin "6") (pinfunction "OUT1_6") (pintype "bidirectional"))
      (node (ref "R31") (pin "2") (pinfunction "2_2") (pintype "passive"))
    )
    (net (code "35") (name "Net-(IC1-OUT2)") (class "Default")
      (node (ref "IC1") (pin "7") (pinfunction "OUT2_7") (pintype "bidirectional"))
      (node (ref "MODE_C") (pin "RED_C") (pinfunction "RED_RED_C") (pintype "bidirectional"))
    )
    (net (code "36") (name "Net-(IC1-OUT3)") (class "Default")
      (node (ref "IC1") (pin "8") (pinfunction "OUT3_8") (pintype "bidirectional"))
      (node (ref "MODE_C") (pin "GREEN_C") (pinfunction "GRN_GREEN_C") (pintype "bidirectional"))
    )
    (net (code "37") (name "Net-(IC1-OUT4)") (class "Default")
      (node (ref "IC1") (pin "9") (pinfunction "OUT4_9") (pintype "bidirectional"))
      (node (ref "MODE_A") (pin "GREEN_C") (pinfunction "GRN_GREEN_C") (pintype "bidirectional"))
    )
    (net (code "38") (name "Net-(IC1-OUT5)") (class "Default")
      (node (ref "IC1") (pin "10") (pinfunction "OUT5_10") (pintype "bidirectional"))
      (node (ref "MODE_A") (pin "RED_C") (pinfunction "RED_RED_C") (pintype "bidirectional"))
    )
    (net (code "39") (name "Net-(IC1-OUT6)") (class "Default")
      (node (ref "IC1") (pin "11") (pinfunction "OUT6_11") (pintype "bidirectional"))
      (node (ref "MODE_B") (pin "GREEN_C") (pinfunction "GRN_GREEN_C") (pintype "bidirectional"))
    )
    (net (code "40") (name "Net-(IC1-OUT7)") (class "Default")
      (node (ref "IC1") (pin "12") (pinfunction "OUT7_12") (pintype "bidirectional"))
      (node (ref "MODE_B") (pin "RED_C") (pinfunction "RED_RED_C") (pintype "bidirectional"))
    )
    (net (code "41") (name "Net-(IC1-OUT8)") (class "Default")
      (node (ref "IC1") (pin "13") (pinfunction "OUT8_13") (pintype "bidirectional"))
      (node (ref "LED10") (pin "GREEN_C") (pinfunction "GRN_GREEN_C") (pintype "bidirectional"))
    )
    (net (code "42") (name "Net-(IC1-OUT9)") (class "Default")
      (node (ref "IC1") (pin "14") (pinfunction "OUT9_14") (pintype "bidirectional"))
      (node (ref "LED10") (pin "RED_C") (pinfunction "RED_RED_C") (pintype "bidirectional"))
    )
    (net (code "43") (name "Net-(IC1-OUT10)") (class "Default")
      (node (ref "IC1") (pin "15") (pinfunction "OUT10_15") (pintype "bidirectional"))
      (node (ref "LED11") (pin "RED_C") (pinfunction "RED_RED_C") (pintype "bidirectional"))
    )
    (net (code "44") (name "Net-(IC1-OUT11)") (class "Default")
      (node (ref "IC1") (pin "16") (pinfunction "OUT11_16") (pintype "bidirectional"))
      (node (ref "LED11") (pin "GREEN_C") (pinfunction "GRN_GREEN_C") (pintype "bidirectional"))
    )
    (net (code "45") (name "Net-(IC1-OUT12)") (class "Default")
      (node (ref "IC1") (pin "17") (pinfunction "OUT12_17") (pintype "bidirectional"))
      (node (ref "LED12") (pin "RED_C") (pinfunction "RED_RED_C") (pintype "bidirectional"))
    )
    (net (code "46") (name "Net-(IC1-OUT13)") (class "Default")
      (node (ref "IC1") (pin "18") (pinfunction "OUT13_18") (pintype "bidirectional"))
      (node (ref "LED12") (pin "GREEN_C") (pinfunction "GRN_GREEN_C") (pintype "bidirectional"))
    )
    (net (code "47") (name "Net-(IC1-OUT14)") (class "Default")
      (node (ref "IC1") (pin "19") (pinfunction "OUT14_19") (pintype "bidirectional"))
      (node (ref "R19") (pin "2") (pinfunction "2_2") (pintype "passive"))
    )
    (net (code "48") (name "Net-(IC1-OUT15)") (class "Default")
      (node (ref "IC1") (pin "20") (pinfunction "OUT15_20") (pintype "bidirectional"))
      (node (ref "R30") (pin "2") (pinfunction "2_2") (pintype "passive"))
    )
    (net (code "49") (name "Net-(IC1-VCC)") (class "Default")
      (node (ref "C7") (pin "1") (pinfunction "1_1") (pintype "passive"))
      (node (ref "C8") (pin "1") (pinfunction "1_1") (pintype "passive"))
      (node (ref "IC1") (pin "24") (pinfunction "VCC_24") (pintype "bidirectional"))
      (node (ref "L2") (pin "1") (pinfunction "1_1") (pintype "passive"))
    )
    (net (code "50") (name "Net-(IC2-VI)") (class "Default")
      (node (ref "C15") (pin "1") (pinfunction "1_1") (pintype "passive"))
      (node (ref "IC2") (pin "1") (pinfunction "VI_1") (pintype "input"))
      (node (ref "L3") (pin "2") (pinfunction "2_2") (pintype "passive"))
    )
    (net (code "51") (name "Net-(IC3A-X0)") (class "Default")
      (node (ref "IC3") (pin "13") (pinfunction "X0_13") (pintype "bidirectional"))
      (node (ref "POT_C") (pin "P$2") (pinfunction "S_P$2") (pintype "passive"))
    )
    (net (code "52") (name "Net-(IC3A-X1)") (class "Default")
      (node (ref "IC3") (pin "14") (pinfunction "X1_14") (pintype "bidirectional"))
      (node (ref "SLD_C") (pin "2") (pinfunction "S_2") (pintype "passive"))
    )
    (net (code "53") (name "Net-(IC3A-X2)") (class "Default")
      (node (ref "IC3") (pin "15") (pinfunction "X2_15") (pintype "bidirectional"))
      (node (ref "SLD_B") (pin "2") (pinfunction "S_2") (pintype "passive"))
    )
    (net (code "54") (name "Net-(IC3A-X3)") (class "Default")
      (node (ref "IC3") (pin "12") (pinfunction "X3_12") (pintype "bidirectional"))
      (node (ref "POT_A") (pin "P$2") (pinfunction "S_P$2") (pintype "passive"))
    )
    (net (code "55") (name "Net-(IC3A-X4)") (class "Default")
      (node (ref "IC3") (pin "1") (pinfunction "X4_1") (pintype "bidirectional"))
      (node (ref "SLD_A") (pin "2") (pinfunction "S_2") (pintype "passive"))
    )
    (net (code "56") (name "Net-(IC3A-X6)") (class "Default")
      (node (ref "IC3") (pin "2") (pinfunction "X6_2") (pintype "bidirectional"))
      (node (ref "POT_B") (pin "P$2") (pinfunction "S_P$2") (pintype "passive"))
    )
    (net (code "57") (name "Net-(IC7-VI)") (class "Default")
      (node (ref "C20") (pin "1") (pinfunction "1_1") (pintype "passive"))
      (node (ref "IC7") (pin "3") (pinfunction "VI_3") (pintype "input"))
      (node (ref "L4") (pin "1") (pinfunction "1_1") (pintype "passive"))
    )
    (net (code "58") (name "Net-(IC9A-+IN)") (class "Default")
      (node (ref "IC9") (pin "3") (pinfunction "+IN_3") (pintype "input"))
      (node (ref "R8") (pin "2") (pinfunction "2_2") (pintype "passive"))
      (node (ref "R9") (pin "1") (pinfunction "1_1") (pintype "passive"))
    )
    (net (code "59") (name "Net-(IC9A--IN)") (class "Default")
      (node (ref "IC9") (pin "2") (pinfunction "-IN_2") (pintype "input"))
      (node (ref "R10") (pin "1") (pinfunction "1_1") (pintype "passive"))
    )
    (net (code "60") (name "Net-(IC9A-OUT)") (class "Default")
      (node (ref "IC9") (pin "1") (pinfunction "OUT_1") (pintype "output"))
      (node (ref "R7") (pin "2") (pinfunction "2_2") (pintype "passive"))
      (node (ref "R8") (pin "1") (pinfunction "1_1") (pintype "passive"))
    )
    (net (code "61") (name "Net-(IC9B-+IN)") (class "Default")
      (node (ref "IC9") (pin "5") (pinfunction "+IN_5") (pintype "input"))
      (node (ref "R12") (pin "2") (pinfunction "2_2") (pintype "passive"))
      (node (ref "R13") (pin "1") (pinfunction "1_1") (pintype "passive"))
    )
    (net (code "62") (name "Net-(IC9B--IN)") (class "Default")
      (node (ref "IC9") (pin "6") (pinfunction "-IN_6") (pintype "input"))
      (node (ref "R14") (pin "1") (pinfunction "1_1") (pintype "passive"))
    )
    (net (code "63") (name "Net-(IC9B-OUT)") (class "Default")
      (node (ref "IC9") (pin "7") (pinfunction "OUT_7") (pintype "output"))
      (node (ref "R11") (pin "2") (pinfunction "2_2") (pintype "passive"))
      (node (ref "R12") (pin "1") (pinfunction "1_1") (pintype "passive"))
    )
    (net (code "64") (name "Net-(IC9C-+IN)") (class "Default")
      (node (ref "IC9") (pin "10") (pinfunction "+IN_10") (pintype "input"))
      (node (ref "R16") (pin "2") (pinfunction "2_2") (pintype "passive"))
      (node (ref "R17") (pin "1") (pinfunction "1_1") (pintype "passive"))
    )
    (net (code "65") (name "Net-(IC9C--IN)") (class "Default")
      (node (ref "IC9") (pin "9") (pinfunction "-IN_9") (pintype "input"))
      (node (ref "R20") (pin "1") (pinfunction "1_1") (pintype "passive"))
    )
    (net (code "66") (name "Net-(IC9C-OUT)") (class "Default")
      (node (ref "IC9") (pin "8") (pinfunction "OUT_8") (pintype "output"))
      (node (ref "R15") (pin "2") (pinfunction "2_2") (pintype "passive"))
      (node (ref "R16") (pin "1") (pinfunction "1_1") (pintype "passive"))
    )
    (net (code "67") (name "Net-(IC9D--IN)") (class "Default")
      (node (ref "IC9") (pin "13") (pinfunction "-IN_13") (pintype "input"))
      (node (ref "IC9") (pin "14") (pinfunction "OUT_14") (pintype "output"))
    )
    (net (code "68") (name "Net-(J2-3)") (class "Default")
      (node (ref "J2") (pin "P3") (pinfunction "3_P3") (pintype "passive"))
      (node (ref "R4") (pin "2") (pinfunction "2_2") (pintype "passive"))
    )
    (net (code "69") (name "Net-(J5-3)") (class "Default")
      (node (ref "J5") (pin "P3") (pinfunction "3_P3") (pintype "passive"))
      (node (ref "R51") (pin "2") (pinfunction "2_2") (pintype "passive"))
    )
    (net (code "70") (name "Net-(J7-3)") (class "Default")
      (node (ref "J7") (pin "P3") (pinfunction "3_P3") (pintype "passive"))
      (node (ref "R27") (pin "1") (pinfunction "1_1") (pintype "passive"))
      (node (ref "R32") (pin "1") (pinfunction "1_1") (pintype "passive"))
    )
    (net (code "71") (name "Net-(J8-3)") (class "Default")
      (node (ref "J8") (pin "P3") (pinfunction "3_P3") (pintype "passive"))
      (node (ref "R23") (pin "1") (pinfunction "1_1") (pintype "passive"))
      (node (ref "R3") (pin "1") (pinfunction "1_1") (pintype "passive"))
    )
    (net (code "72") (name "Net-(J9-3)") (class "Default")
      (node (ref "J9") (pin "P3") (pinfunction "3_P3") (pintype "passive"))
      (node (ref "R35") (pin "1") (pinfunction "1_1") (pintype "passive"))
      (node (ref "R41") (pin "1") (pinfunction "1_1") (pintype "passive"))
    )
    (net (code "73") (name "Net-(J10-3)") (class "Default")
      (node (ref "J10") (pin "P3") (pinfunction "3_P3") (pintype "passive"))
      (node (ref "R11") (pin "1") (pinfunction "1_1") (pintype "passive"))
    )
    (net (code "74") (name "Net-(J11-3)") (class "Default")
      (node (ref "J11") (pin "P3") (pinfunction "3_P3") (pintype "passive"))
      (node (ref "R15") (pin "1") (pinfunction "1_1") (pintype "passive"))
    )
    (net (code "75") (name "Net-(J12-3)") (class "Default")
      (node (ref "J12") (pin "P3") (pinfunction "3_P3") (pintype "passive"))
      (node (ref "R7") (pin "1") (pinfunction "1_1") (pintype "passive"))
    )
    (net (code "76") (name "Net-(Q2B-2)") (class "Default")
      (node (ref "C35") (pin "2") (pinfunction "2_2") (pintype "passive"))
      (node (ref "Q2") (pin "3") (pinfunction "2_3") (pintype "passive"))
      (node (ref "R21") (pin "2") (pinfunction "2_2") (pintype "passive"))
    )
    (net (code "77") (name "Net-(SLD_AA-C)") (class "Default")
      (node (ref "R19") (pin "1") (pinfunction "1_1") (pintype "passive"))
      (node (ref "SLD_A") (pin "E") (pinfunction "C_E") (pintype "passive"))
    )
    (net (code "78") (name "Net-(SLD_BA-C)") (class "Default")
      (node (ref "R30") (pin "1") (pinfunction "1_1") (pintype "passive"))
      (node (ref "SLD_B") (pin "E") (pinfunction "C_E") (pintype "passive"))
    )
    (net (code "79") (name "Net-(SLD_CA-C)") (class "Default")
      (node (ref "R31") (pin "1") (pinfunction "1_1") (pintype "passive"))
      (node (ref "SLD_C") (pin "E") (pinfunction "C_E") (pintype "passive"))
    )
    (net (code "80") (name "Net-(U1-PF0{slash}OSC_IN)") (class "Default")
      (node (ref "R21") (pin "1") (pinfunction "1_1") (pintype "passive"))
      (node (ref "U1") (pin "2") (pinfunction "PF0/OSC_IN_2") (pintype "bidirectional"))
    )
    (net (code "81") (name "Net-(U1-PF1{slash}OSC_OUT)") (class "Default")
      (node (ref "R22") (pin "1") (pinfunction "1_1") (pintype "passive"))
      (node (ref "U1") (pin "3") (pinfunction "PF1/OSC_OUT_3") (pintype "bidirectional"))
    )
    (net (code "82") (name "Net-(U2A--IN)") (class "Default")
      (node (ref "C12") (pin "1") (pinfunction "1_1") (pintype "passive"))
      (node (ref "R29") (pin "1") (pinfunction "1_1") (pintype "passive"))
      (node (ref "R4") (pin "1") (pinfunction "1_1") (pintype "passive"))
      (node (ref "R5") (pin "2") (pinfunction "2_2") (pintype "passive"))
      (node (ref "U2") (pin "2") (pinfunction "-IN_2") (pintype "input"))
    )
    (net (code "83") (name "Net-(U2C--IN)") (class "Default")
      (node (ref "C26") (pin "1") (pinfunction "1_1") (pintype "passive"))
      (node (ref "R26") (pin "2") (pinfunction "2_2") (pintype "passive"))
      (node (ref "R28") (pin "1") (pinfunction "1_1") (pintype "passive"))
      (node (ref "R6") (pin "1") (pinfunction "1_1") (pintype "passive"))
      (node (ref "U2") (pin "9") (pinfunction "-IN_9") (pintype "input"))
    )
    (net (code "84") (name "Net-(U2D--IN)") (class "Default")
      (node (ref "C28") (pin "1") (pinfunction "1_1") (pintype "passive"))
      (node (ref "R51") (pin "1") (pinfunction "1_1") (pintype "passive"))
      (node (ref "R52") (pin "2") (pinfunction "2_2") (pintype "passive"))
      (node (ref "R53") (pin "1") (pinfunction "1_1") (pintype "passive"))
      (node (ref "U2") (pin "13") (pinfunction "-IN_13") (pintype "input"))
    )
    (net (code "85") (name "Net-(U4A--IN)") (class "Default")
      (node (ref "C1") (pin "1") (pinfunction "1_1") (pintype "passive"))
      (node (ref "R2") (pin "1") (pinfunction "1_1") (pintype "passive"))
      (node (ref "R41") (pin "2") (pinfunction "2_2") (pintype "passive"))
      (node (ref "R47") (pin "1") (pinfunction "1_1") (pintype "passive"))
      (node (ref "U4") (pin "2") (pinfunction "-IN_2") (pintype "input"))
    )
    (net (code "86") (name "Net-(U4A-OUT)") (class "Default")
      (node (ref "C1") (pin "2") (pinfunction "2_2") (pintype "passive"))
      (node (ref "R35") (pin "2") (pinfunction "2_2") (pintype "passive"))
      (node (ref "U4") (pin "1") (pinfunction "OUT_1") (pintype "output"))
    )
    (net (code "87") (name "Net-(U4B--IN)") (class "Default")
      (node (ref "C2") (pin "1") (pinfunction "1_1") (pintype "passive"))
      (node (ref "R23") (pin "2") (pinfunction "2_2") (pintype "passive"))
      (node (ref "R24") (pin "1") (pinfunction "1_1") (pintype "passive"))
      (node (ref "R25") (pin "1") (pinfunction "1_1") (pintype "passive"))
      (node (ref "U4") (pin "6") (pinfunction "-IN_6") (pintype "input"))
    )
    (net (code "88") (name "Net-(U4B-OUT)") (class "Default")
      (node (ref "C2") (pin "2") (pinfunction "2_2") (pintype "passive"))
      (node (ref "R3") (pin "2") (pinfunction "2_2") (pintype "passive"))
      (node (ref "U4") (pin "7") (pinfunction "OUT_7") (pintype "output"))
    )
    (net (code "89") (name "Net-(U4C--IN)") (class "Default")
      (node (ref "C3") (pin "1") (pinfunction "1_1") (pintype "passive"))
      (node (ref "R32") (pin "2") (pinfunction "2_2") (pintype "passive"))
      (node (ref "R33") (pin "1") (pinfunction "1_1") (pintype "passive"))
      (node (ref "R34") (pin "1") (pinfunction "1_1") (pintype "passive"))
      (node (ref "U4") (pin "9") (pinfunction "-IN_9") (pintype "input"))
    )
    (net (code "90") (name "Net-(U4C-OUT)") (class "Default")
      (node (ref "C3") (pin "2") (pinfunction "2_2") (pintype "passive"))
      (node (ref "R27") (pin "2") (pinfunction "2_2") (pintype "passive"))
      (node (ref "U4") (pin "8") (pinfunction "OUT_8") (pintype "output"))
    )
    (net (code "91") (name "Net-(U4D--IN)") (class "Default")
      (node (ref "U4") (pin "13") (pinfunction "-IN_13") (pintype "input"))
      (node (ref "U4") (pin "14") (pinfunction "OUT_14") (pintype "output"))
    )
    (net (code "92") (name "POTS_ADDR_A") (class "Default")
      (node (ref "IC3") (pin "11") (pinfunction "A_11") (pintype "input"))
      (node (ref "U1") (pin "13") (pinfunction "PA7_13") (pintype "bidirectional"))
    )
    (net (code "93") (name "POTS_ADDR_B") (class "Default")
      (node (ref "IC3") (pin "10") (pinfunction "B_10") (pintype "input"))
      (node (ref "U1") (pin "18") (pinfunction "PA8_18") (pintype "bidirectional"))
    )
    (net (code "94") (name "POTS_ADDR_C") (class "Default")
      (node (ref "IC3") (pin "9") (pinfunction "C_9") (pintype "input"))
      (node (ref "U1") (pin "19") (pinfunction "PA9_19") (pintype "bidirectional"))
    )
    (net (code "95") (name "RESET") (class "Default")
      (node (ref "C36") (pin "1") (pinfunction "1_1") (pintype "passive"))
      (node (ref "JP6") (pin "4") (pinfunction "4_4") (pintype "passive"))
      (node (ref "R18") (pin "2") (pinfunction "2_2") (pintype "passive"))
      (node (ref "U1") (pin "4") (pinfunction "NRST_4") (pintype "bidirectional"))
    )
    (net (code "96") (name "SWCLK") (class "Default")
      (node (ref "JP6") (pin "3") (pinfunction "3_3") (pintype "passive"))
      (node (ref "U1") (pin "24") (pinfunction "PA14_24") (pintype "bidirectional"))
    )
    (net (code "97") (name "SWDIO") (class "Default")
      (node (ref "JP6") (pin "2") (pinfunction "2_2") (pintype "passive"))
      (node (ref "U1") (pin "23") (pinfunction "PA13_23") (pintype "bidirectional"))
    )
    (net (code "98") (name "SW_MODE_A") (class "Default")
      (node (ref "SW_A") (pin "3") (pinfunction "3_3") (pintype "passive"))
      (node (ref "SW_A") (pin "4") (pinfunction "4_4") (pintype "passive"))
      (node (ref "U1") (pin "27") (pinfunction "PB4_27") (pintype "bidirectional"))
    )
    (net (code "99") (name "SW_MODE_B") (class "Default")
      (node (ref "SW_B") (pin "3") (pinfunction "3_3") (pintype "passive"))
      (node (ref "SW_B") (pin "4") (pinfunction "4_4") (pintype "passive"))
      (node (ref "U1") (pin "29") (pinfunction "PB6_29") (pintype "bidirectional"))
    )
    (net (code "100") (name "SW_MODE_C") (class "Default")
      (node (ref "SW_C") (pin "3") (pinfunction "3_3") (pintype "passive"))
      (node (ref "SW_C") (pin "4") (pinfunction "4_4") (pintype "passive"))
      (node (ref "U1") (pin "30") (pinfunction "PB7_30") (pintype "bidirectional"))
    )
    (net (code "101") (name "VCC") (class "Default")
      (node (ref "C14") (pin "1") (pinfunction "1_1") (pintype "passive"))
      (node (ref "C21") (pin "1") (pinfunction "1_1") (pintype "passive"))
      (node (ref "C4") (pin "1") (pinfunction "1_1") (pintype "passive"))
      (node (ref "C50") (pin "1") (pinfunction "1_1") (pintype "passive"))
      (node (ref "IC9") (pin "4") (pinfunction "V+_4") (pintype "power_in"))
      (node (ref "L5") (pin "1") (pinfunction "1_1") (pintype "passive"))
      (node (ref "U4") (pin "4") (pinfunction "V+_4") (pintype "power_in"))
    )
    (net (code "102") (name "VEE") (class "Default")
      (node (ref "C16") (pin "2") (pinfunction "2_2") (pintype "passive"))
      (node (ref "C18") (pin "2") (pinfunction "2_2") (pintype "passive"))
      (node (ref "C23") (pin "2") (pinfunction "2_2") (pintype "passive"))
      (node (ref "L1") (pin "1") (pinfunction "1_1") (pintype "passive"))
      (node (ref "R1") (pin "1") (pinfunction "1_1") (pintype "passive"))
      (node (ref "U4") (pin "11") (pinfunction "V-_11") (pintype "power_in"))
    )
    (net (code "103") (name "unconnected-(IC1-LAT-Pad4)") (class "Default")
      (node (ref "IC1") (pin "4") (pinfunction "LAT_4") (pintype "bidirectional"))
    )
    (net (code "104") (name "unconnected-(IC1-OUT0-Pad5)") (class "Default")
      (node (ref "IC1") (pin "5") (pinfunction "OUT0_5") (pintype "bidirectional"))
    )
    (net (code "105") (name "unconnected-(IC1-SOUT-Pad22)") (class "Default")
      (node (ref "IC1") (pin "22") (pinfunction "SOUT_22") (pintype "bidirectional"))
    )
    (net (code "106") (name "unconnected-(IC3A-X5-Pad5)") (class "Default")
      (node (ref "IC3") (pin "5") (pinfunction "X5_5") (pintype "bidirectional"))
    )
    (net (code "107") (name "unconnected-(IC3A-X7-Pad4)") (class "Default")
      (node (ref "IC3") (pin "4") (pinfunction "X7_4") (pintype "bidirectional"))
    )
    (net (code "108") (name "unconnected-(J7-2-PadP2)") (class "Default")
      (node (ref "J7") (pin "P2") (pinfunction "2_P2") (pintype "passive"))
    )
    (net (code "109") (name "unconnected-(J8-2-PadP2)") (class "Default")
      (node (ref "J8") (pin "P2") (pinfunction "2_P2") (pintype "passive"))
    )
    (net (code "110") (name "unconnected-(J9-2-PadP2)") (class "Default")
      (node (ref "J9") (pin "P2") (pinfunction "2_P2") (pintype "passive"))
    )
    (net (code "111") (name "unconnected-(J10-2-PadP2)") (class "Default")
      (node (ref "J10") (pin "P2") (pinfunction "2_P2") (pintype "passive"))
    )
    (net (code "112") (name "unconnected-(J11-2-PadP2)") (class "Default")
      (node (ref "J11") (pin "P2") (pinfunction "2_P2") (pintype "passive"))
    )
    (net (code "113") (name "unconnected-(J12-2-PadP2)") (class "Default")
      (node (ref "J12") (pin "P2") (pinfunction "2_P2") (pintype "passive"))
    )
  )
)
